# espAlarm.net
KiCad netlist of a schematic drawn in EAGLE
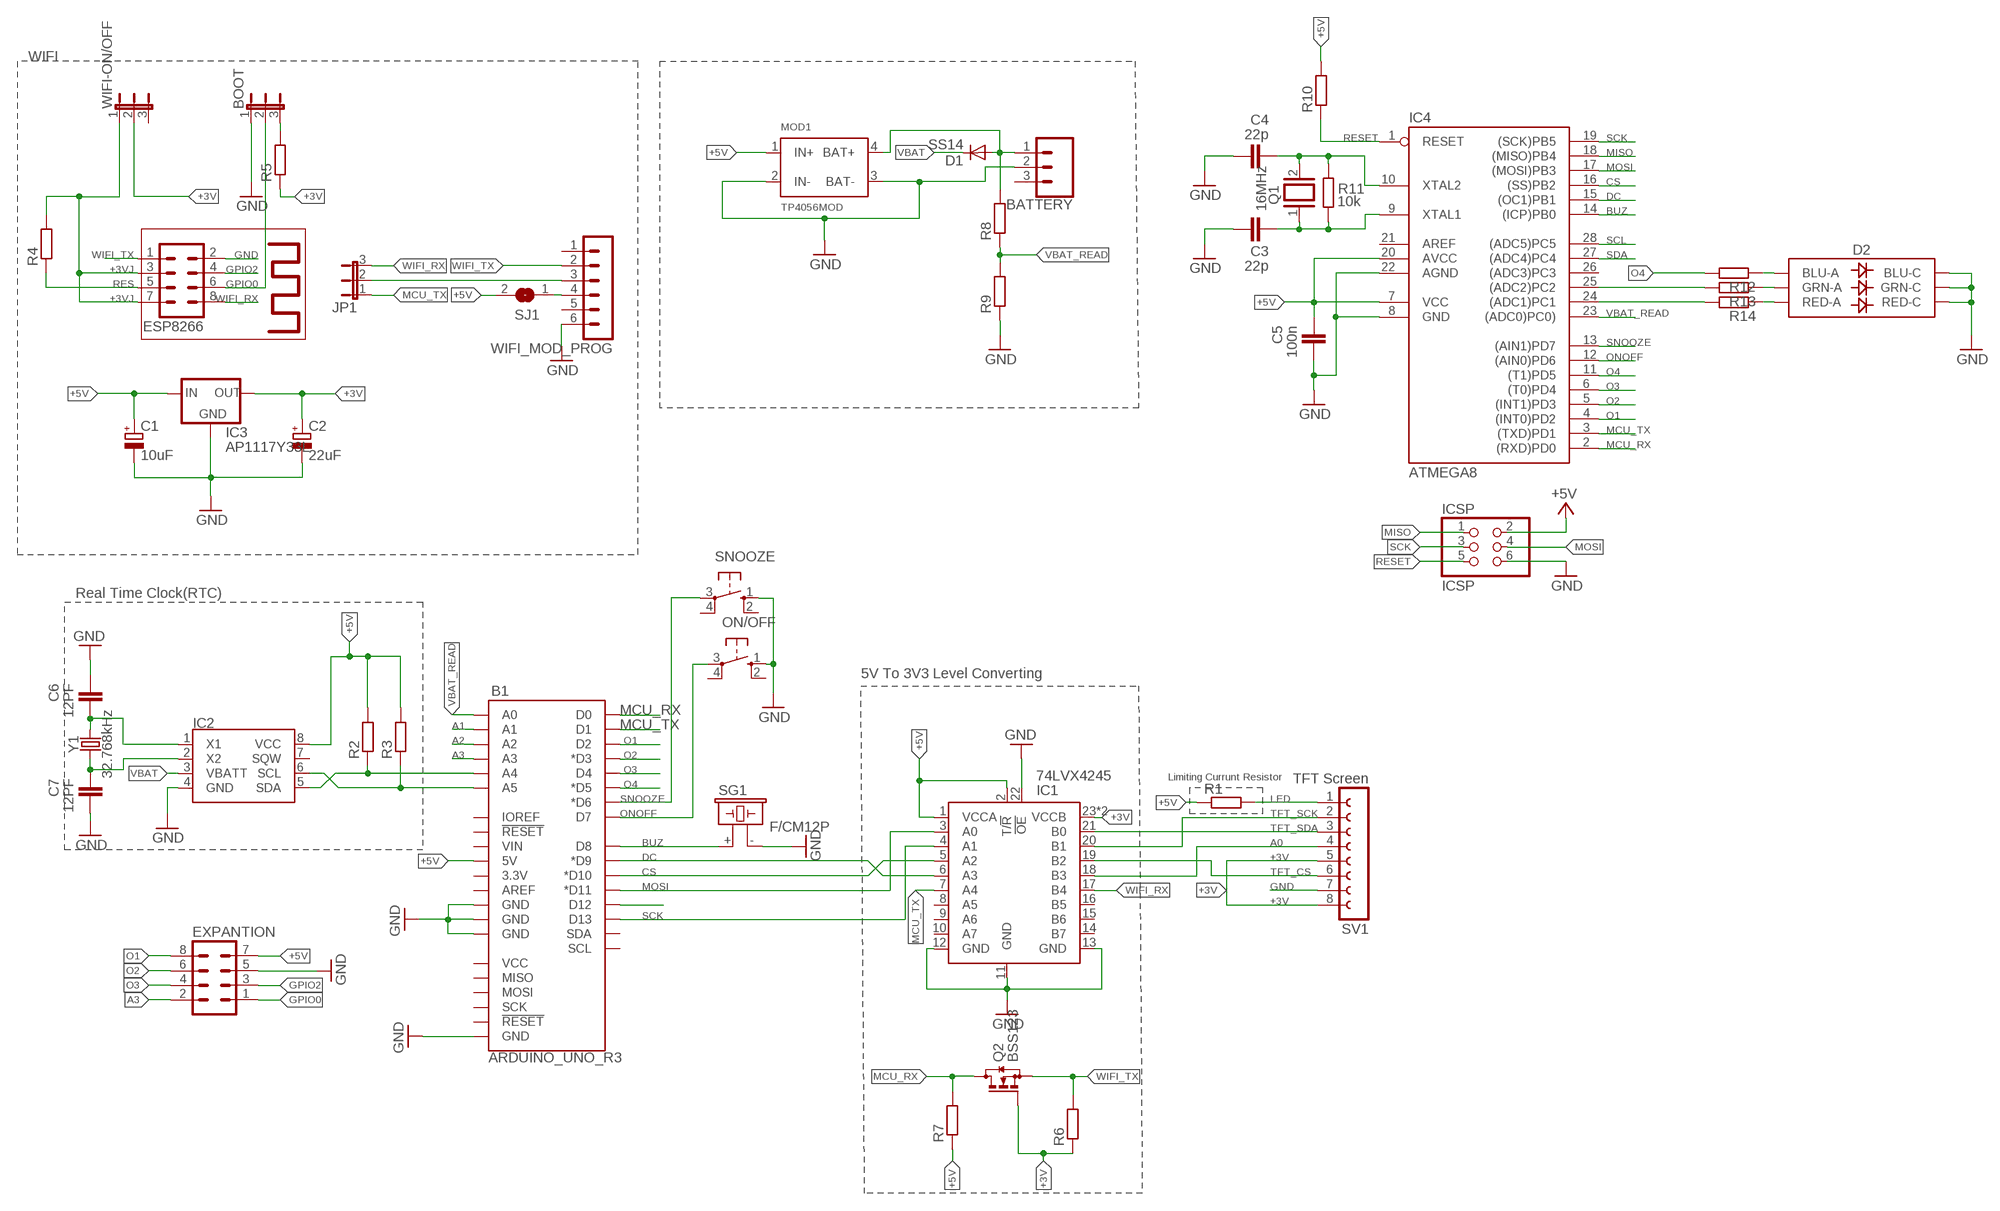
[diagram p0: schematic, sheet 1]

(export (version "E")
  (design (tool "Eeschema 10.0.6"))
  (components
    (comp (ref "B1")
      (value "ARDUINO_UNO_R3")
      (footprint "eagle-import:ARDUINO_R3")
      (libsource (lib "eagle-import") (part "ARDUINO_UNO_R3"))
    )
    (comp (ref "BATTERY")
      (value "CONN_03JST-PTH-VERT")
      (footprint "eagle-import:JST-3-PTH-VERT")
      (libsource (lib "eagle-import") (part "CONN_03JST-PTH-VERT"))
    )
    (comp (ref "BOOT")
      (value "JP2E")
      (footprint "eagle-import:JP2")
      (libsource (lib "eagle-import") (part "JP2E"))
    )
    (comp (ref "C1")
      (value "10uF")
      (footprint "eagle-import:E2,5-7")
      (libsource (lib "eagle-import") (part "CPOL-EUE2.5-7"))
    )
    (comp (ref "C2")
      (value "22uF")
      (footprint "eagle-import:E2,5-7")
      (libsource (lib "eagle-import") (part "CPOL-EUE2.5-7"))
    )
    (comp (ref "C3")
      (value "22p")
      (footprint "eagle-import:C0805")
      (libsource (lib "eagle-import") (part "C-EUC0805"))
    )
    (comp (ref "C4")
      (value "22p")
      (footprint "eagle-import:C0805")
      (libsource (lib "eagle-import") (part "C-EUC0805"))
    )
    (comp (ref "C5")
      (value "100n")
      (footprint "eagle-import:C0805")
      (libsource (lib "eagle-import") (part "C-EUC0805"))
    )
    (comp (ref "C6")
      (value "12PF")
      (footprint "eagle-import:C0805")
      (libsource (lib "eagle-import") (part "C-EUC0805"))
    )
    (comp (ref "C7")
      (value "12PF")
      (footprint "eagle-import:C0805")
      (libsource (lib "eagle-import") (part "C-EUC0805"))
    )
    (comp (ref "D1")
      (value "SS14")
      (footprint "eagle-import:DO214AC")
      (libsource (lib "eagle-import") (part "DIODE-DO214AC"))
    )
    (comp (ref "D2")
      (value "LED-RGBNO_IC")
      (footprint "eagle-import:LED-TRICOLOR-5050")
      (libsource (lib "eagle-import") (part "LED-RGBNO_IC"))
    )
    (comp (ref "ESP8266")
      (value "MA04-2")
      (footprint "eagle-import:MA04-2")
      (libsource (lib "eagle-import") (part "MA04-2"))
    )
    (comp (ref "EXPANTION")
      (value "MA04-2")
      (footprint "eagle-import:MA04-2")
      (libsource (lib "eagle-import") (part "MA04-2"))
    )
    (comp (ref "IC1")
      (value "74LVX4245")
      (footprint "eagle-import:TSSOP-24")
      (libsource (lib "eagle-import") (part "74LVX4245"))
    )
    (comp (ref "IC2")
      (value "DS1307")
      (footprint "eagle-import:DIP-08")
      (libsource (lib "eagle-import") (part "DS1307"))
    )
    (comp (ref "IC3")
      (value "AP1117Y33L")
      (footprint "eagle-import:SOT-89-3")
      (libsource (lib "eagle-import") (part "REG_FIXED"))
    )
    (comp (ref "IC4")
      (value "ATMEGA8")
      (footprint "eagle-import:DIL28-3")
      (libsource (lib "eagle-import") (part "AT90S4433P"))
    )
    (comp (ref "ICSP")
      (value "ICSP")
      (footprint "eagle-import:2X03")
      (libsource (lib "eagle-import") (part "PINHD-2X3"))
    )
    (comp (ref "JP1")
      (value "JP2E")
      (footprint "eagle-import:JP2")
      (libsource (lib "eagle-import") (part "JP2E"))
    )
    (comp (ref "MOD1")
      (value "TP4056MOD")
      (footprint "eagle-import:TP4056BRD")
      (libsource (lib "eagle-import") (part "TP4056MOD"))
    )
    (comp (ref "ON/OFF")
      (value "10-XX")
      (footprint "eagle-import:B3F-10XX")
      (fields (field (name "MPN") "B3F-1000"))
      (libsource (lib "eagle-import") (part "10-XX"))
    )
    (comp (ref "Q1")
      (value "16MHz")
      (footprint "eagle-import:SMARTPRJ_QS")
      (libsource (lib "eagle-import") (part "SMARTPRJ_XTAL/S"))
    )
    (comp (ref "Q2")
      (value "BSS123")
      (footprint "eagle-import:SOT23")
      (libsource (lib "eagle-import") (part "BSS123"))
    )
    (comp (ref "R1")
      (value "R-EU_M1206")
      (footprint "eagle-import:M1206")
      (libsource (lib "eagle-import") (part "R-EU_M1206"))
    )
    (comp (ref "R2")
      (value "R-EU_M1206")
      (footprint "eagle-import:M1206")
      (libsource (lib "eagle-import") (part "R-EU_M1206"))
    )
    (comp (ref "R3")
      (value "R-EU_M1206")
      (footprint "eagle-import:M1206")
      (libsource (lib "eagle-import") (part "R-EU_M1206"))
    )
    (comp (ref "R4")
      (value "R-EU_M1206")
      (footprint "eagle-import:M1206")
      (libsource (lib "eagle-import") (part "R-EU_M1206"))
    )
    (comp (ref "R5")
      (value "R-EU_M1206")
      (footprint "eagle-import:M1206")
      (libsource (lib "eagle-import") (part "R-EU_M1206"))
    )
    (comp (ref "R6")
      (value "R-EU_M1206")
      (footprint "eagle-import:M1206")
      (libsource (lib "eagle-import") (part "R-EU_M1206"))
    )
    (comp (ref "R7")
      (value "R-EU_M1206")
      (footprint "eagle-import:M1206")
      (libsource (lib "eagle-import") (part "R-EU_M1206"))
    )
    (comp (ref "R8")
      (value "R-EU_M1206")
      (footprint "eagle-import:M1206")
      (libsource (lib "eagle-import") (part "R-EU_M1206"))
    )
    (comp (ref "R9")
      (value "R-EU_M1206")
      (footprint "eagle-import:M1206")
      (libsource (lib "eagle-import") (part "R-EU_M1206"))
    )
    (comp (ref "R10")
      (value "R-EU_M1206")
      (footprint "eagle-import:M1206")
      (libsource (lib "eagle-import") (part "R-EU_M1206"))
    )
    (comp (ref "R11")
      (value "10k")
      (footprint "eagle-import:M1206")
      (libsource (lib "eagle-import") (part "R-EU_M1206"))
    )
    (comp (ref "R12")
      (value "R-EU_M1206")
      (footprint "eagle-import:M1206")
      (libsource (lib "eagle-import") (part "R-EU_M1206"))
    )
    (comp (ref "R13")
      (value "R-EU_M1206")
      (footprint "eagle-import:M1206")
      (libsource (lib "eagle-import") (part "R-EU_M1206"))
    )
    (comp (ref "R14")
      (value "R-EU_M1206")
      (footprint "eagle-import:M1206")
      (libsource (lib "eagle-import") (part "R-EU_M1206"))
    )
    (comp (ref "SG1")
      (value "F/CM12P")
      (footprint "eagle-import:F_CM12P")
      (libsource (lib "eagle-import") (part "F/CM12P"))
    )
    (comp (ref "SJ1") (value "SJ") (footprint "eagle-import:SJ") (libsource (lib "eagle-import") (part "SJ")))
    (comp (ref "SNOOZE")
      (value "10-XX")
      (footprint "eagle-import:B3F-10XX")
      (fields (field (name "MPN") "B3F-1000"))
      (libsource (lib "eagle-import") (part "10-XX"))
    )
    (comp (ref "SV1")
      (value "TFT Screen")
      (footprint "eagle-import:FE08")
      (libsource (lib "eagle-import") (part "FE08-1"))
    )
    (comp (ref "WIFI-ON/OFF")
      (value "JP2E")
      (footprint "eagle-import:JP2")
      (libsource (lib "eagle-import") (part "JP2E"))
    )
    (comp (ref "WIFI_MOD_PROG")
      (value "MA06-1")
      (footprint "eagle-import:MA06-1")
      (libsource (lib "eagle-import") (part "MA06-1"))
    )
    (comp (ref "Y1")
      (value "32.768kHz")
      (footprint "eagle-import:CRYSTAL-PTH-2X6-CYL")
      (libsource (lib "eagle-import") (part "CRYSTAL-32.768KHZPTH-2X6"))
    )
  )
  (nets
    (net (code "1") (name "+3V") (class "Default")
      (node (ref "C2") (pin "+") (pinfunction "+_+") (pintype "passive"))
      (node (ref "IC1") (pin "23") (pinfunction "VCCB_23") (pintype "power_in"))
      (node (ref "IC1") (pin "24") (pinfunction "VCCB_24") (pintype "power_in"))
      (node (ref "IC3") (pin "3") (pinfunction "OUT_3") (pintype "passive"))
      (node (ref "IC3") (pin "4") (pinfunction "OUT_4") (pintype "passive"))
      (node (ref "Q2") (pin "1") (pinfunction "G_1") (pintype "passive"))
      (node (ref "R5") (pin "1") (pinfunction "1_1") (pintype "passive"))
      (node (ref "R6") (pin "1") (pinfunction "1_1") (pintype "passive"))
      (node (ref "SV1") (pin "5") (pinfunction "5_5") (pintype "passive"))
      (node (ref "SV1") (pin "8") (pinfunction "8_8") (pintype "passive"))
      (node (ref "WIFI-ON/OFF") (pin "2") (pinfunction "2_2") (pintype "passive"))
    )
    (net (code "2") (name "+5V") (class "Default")
      (node (ref "B1") (pin "5V") (pinfunction "5V_5V") (pintype "bidirectional"))
      (node (ref "C1") (pin "+") (pinfunction "+_+") (pintype "passive"))
      (node (ref "C5") (pin "2") (pinfunction "2_2") (pintype "passive"))
      (node (ref "EXPANTION") (pin "7") (pinfunction "7_7") (pintype "passive"))
      (node (ref "IC1") (pin "1") (pinfunction "VCCA_1") (pintype "power_in"))
      (node (ref "IC1") (pin "2") (pinfunction "T/~{R}_2") (pintype "open_collector"))
      (node (ref "IC2") (pin "8") (pinfunction "VCC_8") (pintype "bidirectional"))
      (node (ref "IC3") (pin "1") (pinfunction "IN_1") (pintype "input"))
      (node (ref "IC4") (pin "20") (pinfunction "AVCC_20") (pintype "power_in"))
      (node (ref "IC4") (pin "7") (pinfunction "VCC_7") (pintype "power_in"))
      (node (ref "ICSP") (pin "2") (pinfunction "2_2") (pintype "passive"))
      (node (ref "MOD1") (pin "1") (pinfunction "IN+_1") (pintype "bidirectional"))
      (node (ref "R1") (pin "1") (pinfunction "1_1") (pintype "passive"))
      (node (ref "R10") (pin "2") (pinfunction "2_2") (pintype "passive"))
      (node (ref "R2") (pin "2") (pinfunction "2_2") (pintype "passive"))
      (node (ref "R3") (pin "2") (pinfunction "2_2") (pintype "passive"))
      (node (ref "R7") (pin "1") (pinfunction "1_1") (pintype "passive"))
      (node (ref "SJ1") (pin "2") (pinfunction "2_2") (pintype "passive"))
    )
    (net (code "3") (name "/+3VJ") (class "Default")
      (node (ref "ESP8266") (pin "3") (pinfunction "3_3") (pintype "passive"))
      (node (ref "ESP8266") (pin "7") (pinfunction "7_7") (pintype "passive"))
      (node (ref "R4") (pin "2") (pinfunction "2_2") (pintype "passive"))
      (node (ref "WIFI-ON/OFF") (pin "1") (pinfunction "1_1") (pintype "passive"))
    )
    (net (code "4") (name "/A0") (class "Default")
      (node (ref "IC1") (pin "18") (pinfunction "B3_18") (pintype "bidirectional"))
      (node (ref "SV1") (pin "4") (pinfunction "4_4") (pintype "passive"))
    )
    (net (code "5") (name "/A1") (class "Default")
      (node (ref "B1") (pin "A1") (pinfunction "A1_A1") (pintype "bidirectional"))
      (node (ref "IC4") (pin "24") (pinfunction "(ADC1)PC1_24") (pintype "bidirectional"))
      (node (ref "R14") (pin "2") (pinfunction "2_2") (pintype "passive"))
    )
    (net (code "6") (name "/A2") (class "Default")
      (node (ref "B1") (pin "A2") (pinfunction "A2_A2") (pintype "bidirectional"))
      (node (ref "IC4") (pin "25") (pinfunction "(ADC2)PC2_25") (pintype "bidirectional"))
      (node (ref "R13") (pin "2") (pinfunction "2_2") (pintype "passive"))
    )
    (net (code "7") (name "/AREF") (class "Default")
      (node (ref "IC4") (pin "21") (pinfunction "AREF_21") (pintype "power_in"))
    )
    (net (code "8") (name "/BUZ") (class "Default")
      (node (ref "B1") (pin "D8") (pinfunction "D8_D8") (pintype "bidirectional"))
      (node (ref "IC4") (pin "14") (pinfunction "(ICP)PB0_14") (pintype "bidirectional"))
      (node (ref "SG1") (pin "+") (pinfunction "1_+") (pintype "passive"))
    )
    (net (code "9") (name "/CS") (class "Default")
      (node (ref "B1") (pin "D10") (pinfunction "*D10_D10") (pintype "bidirectional"))
      (node (ref "IC1") (pin "5") (pinfunction "A2_5") (pintype "bidirectional"))
      (node (ref "IC4") (pin "16") (pinfunction "(SS)PB2_16") (pintype "bidirectional"))
    )
    (net (code "10") (name "/DC") (class "Default")
      (node (ref "B1") (pin "D9") (pinfunction "*D9_D9") (pintype "bidirectional"))
      (node (ref "IC1") (pin "6") (pinfunction "A3_6") (pintype "bidirectional"))
      (node (ref "IC4") (pin "15") (pinfunction "(OC1)PB1_15") (pintype "bidirectional"))
    )
    (net (code "11") (name "/LED") (class "Default")
      (node (ref "R1") (pin "2") (pinfunction "2_2") (pintype "passive"))
      (node (ref "SV1") (pin "1") (pinfunction "1_1") (pintype "passive"))
    )
    (net (code "12") (name "/ONOFF") (class "Default")
      (node (ref "B1") (pin "D7") (pinfunction "D7_D7") (pintype "bidirectional"))
      (node (ref "IC4") (pin "12") (pinfunction "(AIN0)PD6_12") (pintype "bidirectional"))
      (node (ref "ON/OFF") (pin "3") (pinfunction "P_3") (pintype "passive"))
    )
    (net (code "13") (name "/RES") (class "Default")
      (node (ref "ESP8266") (pin "5") (pinfunction "5_5") (pintype "passive"))
      (node (ref "R4") (pin "1") (pinfunction "1_1") (pintype "passive"))
    )
    (net (code "14") (name "/SCL") (class "Default")
      (node (ref "B1") (pin "A5") (pinfunction "A5_A5") (pintype "bidirectional"))
      (node (ref "IC2") (pin "6") (pinfunction "SCL_6") (pintype "bidirectional"))
      (node (ref "IC4") (pin "28") (pinfunction "(ADC5)PC5_28") (pintype "bidirectional"))
      (node (ref "R3") (pin "1") (pinfunction "1_1") (pintype "passive"))
    )
    (net (code "15") (name "/SDA") (class "Default")
      (node (ref "B1") (pin "A4") (pinfunction "A4_A4") (pintype "bidirectional"))
      (node (ref "IC2") (pin "5") (pinfunction "SDA_5") (pintype "bidirectional"))
      (node (ref "IC4") (pin "27") (pinfunction "(ADC4)PC4_27") (pintype "bidirectional"))
      (node (ref "R2") (pin "1") (pinfunction "1_1") (pintype "passive"))
    )
    (net (code "16") (name "/SNOOZE") (class "Default")
      (node (ref "B1") (pin "D6") (pinfunction "*D6_D6") (pintype "bidirectional"))
      (node (ref "IC4") (pin "13") (pinfunction "(AIN1)PD7_13") (pintype "bidirectional"))
      (node (ref "SNOOZE") (pin "3") (pinfunction "P_3") (pintype "passive"))
    )
    (net (code "17") (name "/TFT_CS") (class "Default")
      (node (ref "IC1") (pin "19") (pinfunction "B2_19") (pintype "bidirectional"))
      (node (ref "SV1") (pin "6") (pinfunction "6_6") (pintype "passive"))
    )
    (net (code "18") (name "/TFT_SCK") (class "Default")
      (node (ref "IC1") (pin "20") (pinfunction "B1_20") (pintype "bidirectional"))
      (node (ref "SV1") (pin "2") (pinfunction "2_2") (pintype "passive"))
    )
    (net (code "19") (name "/TFT_SDA") (class "Default")
      (node (ref "IC1") (pin "21") (pinfunction "B0_21") (pintype "bidirectional"))
      (node (ref "SV1") (pin "3") (pinfunction "3_3") (pintype "passive"))
    )
    (net (code "20") (name "A3") (class "Default")
      (node (ref "B1") (pin "A3") (pinfunction "A3_A3") (pintype "bidirectional"))
      (node (ref "EXPANTION") (pin "2") (pinfunction "2_2") (pintype "passive"))
    )
    (net (code "21") (name "GND") (class "Default")
      (node (ref "B1") (pin "GND@1") (pinfunction "GND_GND@1") (pintype "bidirectional"))
      (node (ref "B1") (pin "GND@2") (pinfunction "GND_GND@2") (pintype "bidirectional"))
      (node (ref "B1") (pin "GND@3") (pinfunction "GND_GND@3") (pintype "bidirectional"))
      (node (ref "B1") (pin "GND@4") (pinfunction "GND_GND@4") (pintype "bidirectional"))
      (node (ref "BATTERY") (pin "2") (pinfunction "2_2") (pintype "passive"))
      (node (ref "BOOT") (pin "1") (pinfunction "1_1") (pintype "passive"))
      (node (ref "C1") (pin "-") (pinfunction "-_-") (pintype "passive"))
      (node (ref "C2") (pin "-") (pinfunction "-_-") (pintype "passive"))
      (node (ref "C3") (pin "1") (pinfunction "1_1") (pintype "passive"))
      (node (ref "C4") (pin "1") (pinfunction "1_1") (pintype "passive"))
      (node (ref "C5") (pin "1") (pinfunction "1_1") (pintype "passive"))
      (node (ref "C6") (pin "2") (pinfunction "2_2") (pintype "passive"))
      (node (ref "C7") (pin "1") (pinfunction "1_1") (pintype "passive"))
      (node (ref "D2") (pin "4") (pinfunction "BLU-C_4") (pintype "bidirectional"))
      (node (ref "D2") (pin "5") (pinfunction "RED-C_5") (pintype "bidirectional"))
      (node (ref "D2") (pin "6") (pinfunction "GRN-C_6") (pintype "bidirectional"))
      (node (ref "ESP8266") (pin "2") (pinfunction "2_2") (pintype "passive"))
      (node (ref "EXPANTION") (pin "5") (pinfunction "5_5") (pintype "passive"))
      (node (ref "IC1") (pin "11") (pinfunction "GND_11") (pintype "power_in"))
      (node (ref "IC1") (pin "12") (pinfunction "GND_12") (pintype "power_in"))
      (node (ref "IC1") (pin "13") (pinfunction "GND_13") (pintype "power_in"))
      (node (ref "IC1") (pin "22") (pinfunction "~{OE}_22") (pintype "open_collector"))
      (node (ref "IC2") (pin "4") (pinfunction "GND_4") (pintype "bidirectional"))
      (node (ref "IC3") (pin "2") (pinfunction "GND_2") (pintype "input"))
      (node (ref "IC4") (pin "22") (pinfunction "AGND_22") (pintype "power_in"))
      (node (ref "IC4") (pin "8") (pinfunction "GND_8") (pintype "power_in"))
      (node (ref "ICSP") (pin "6") (pinfunction "6_6") (pintype "passive"))
      (node (ref "MOD1") (pin "2") (pinfunction "IN-_2") (pintype "bidirectional"))
      (node (ref "MOD1") (pin "3") (pinfunction "BAT-_3") (pintype "bidirectional"))
      (node (ref "ON/OFF") (pin "1") (pinfunction "S_1") (pintype "passive"))
      (node (ref "R9") (pin "1") (pinfunction "1_1") (pintype "passive"))
      (node (ref "SG1") (pin "-") (pinfunction "2_-") (pintype "passive"))
      (node (ref "SNOOZE") (pin "1") (pinfunction "S_1") (pintype "passive"))
      (node (ref "SV1") (pin "7") (pinfunction "7_7") (pintype "passive"))
      (node (ref "WIFI_MOD_PROG") (pin "6") (pinfunction "6_6") (pintype "passive"))
    )
    (net (code "22") (name "GPIO0") (class "Default")
      (node (ref "BOOT") (pin "2") (pinfunction "2_2") (pintype "passive"))
      (node (ref "ESP8266") (pin "6") (pinfunction "6_6") (pintype "passive"))
      (node (ref "EXPANTION") (pin "1") (pinfunction "1_1") (pintype "passive"))
    )
    (net (code "23") (name "GPIO2") (class "Default")
      (node (ref "ESP8266") (pin "4") (pinfunction "4_4") (pintype "passive"))
      (node (ref "EXPANTION") (pin "3") (pinfunction "3_3") (pintype "passive"))
    )
    (net (code "24") (name "MCU_RX") (class "Default")
      (node (ref "B1") (pin "D0") (pinfunction "D0_D0") (pintype "bidirectional"))
      (node (ref "IC4") (pin "2") (pinfunction "(RXD)PD0_2") (pintype "bidirectional"))
      (node (ref "Q2") (pin "3") (pinfunction "D_3") (pintype "passive"))
      (node (ref "R7") (pin "2") (pinfunction "2_2") (pintype "passive"))
    )
    (net (code "25") (name "MCU_TX") (class "Default")
      (node (ref "B1") (pin "D1") (pinfunction "D1_D1") (pintype "bidirectional"))
      (node (ref "IC1") (pin "7") (pinfunction "A4_7") (pintype "bidirectional"))
      (node (ref "IC4") (pin "3") (pinfunction "(TXD)PD1_3") (pintype "bidirectional"))
      (node (ref "JP1") (pin "1") (pinfunction "1_1") (pintype "passive"))
    )
    (net (code "26") (name "MISO") (class "Default")
      (node (ref "IC4") (pin "18") (pinfunction "(MISO)PB4_18") (pintype "bidirectional"))
      (node (ref "ICSP") (pin "1") (pinfunction "1_1") (pintype "passive"))
    )
    (net (code "27") (name "MOSI") (class "Default")
      (node (ref "B1") (pin "D11") (pinfunction "*D11_D11") (pintype "bidirectional"))
      (node (ref "IC1") (pin "3") (pinfunction "A0_3") (pintype "bidirectional"))
      (node (ref "IC4") (pin "17") (pinfunction "(MOSI)PB3_17") (pintype "bidirectional"))
      (node (ref "ICSP") (pin "4") (pinfunction "4_4") (pintype "passive"))
    )
    (net (code "28") (name "Net-(BOOT-Pad3)") (class "Default")
      (node (ref "BOOT") (pin "3") (pinfunction "3_3") (pintype "passive"))
      (node (ref "R5") (pin "2") (pinfunction "2_2") (pintype "passive"))
    )
    (net (code "29") (name "Net-(D2-BLU-A)") (class "Default")
      (node (ref "D2") (pin "3") (pinfunction "BLU-A_3") (pintype "bidirectional"))
      (node (ref "R12") (pin "1") (pinfunction "1_1") (pintype "passive"))
    )
    (net (code "30") (name "Net-(D2-GRN-A)") (class "Default")
      (node (ref "D2") (pin "1") (pinfunction "GRN-A_1") (pintype "bidirectional"))
      (node (ref "R13") (pin "1") (pinfunction "1_1") (pintype "passive"))
    )
    (net (code "31") (name "Net-(D2-RED-A)") (class "Default")
      (node (ref "D2") (pin "2") (pinfunction "RED-A_2") (pintype "bidirectional"))
      (node (ref "R14") (pin "1") (pinfunction "1_1") (pintype "passive"))
    )
    (net (code "32") (name "Net-(IC2-X1)") (class "Default")
      (node (ref "C6") (pin "1") (pinfunction "1_1") (pintype "passive"))
      (node (ref "IC2") (pin "1") (pinfunction "X1_1") (pintype "bidirectional"))
      (node (ref "Y1") (pin "2") (pinfunction "2_2") (pintype "passive"))
    )
    (net (code "33") (name "Net-(IC2-X2)") (class "Default")
      (node (ref "C7") (pin "2") (pinfunction "2_2") (pintype "passive"))
      (node (ref "IC2") (pin "2") (pinfunction "X2_2") (pintype "bidirectional"))
      (node (ref "Y1") (pin "1") (pinfunction "1_1") (pintype "passive"))
    )
    (net (code "34") (name "Net-(IC4-XTAL1)") (class "Default")
      (node (ref "C3") (pin "2") (pinfunction "2_2") (pintype "passive"))
      (node (ref "IC4") (pin "9") (pinfunction "XTAL1_9") (pintype "bidirectional"))
      (node (ref "Q1") (pin "1") (pinfunction "1_1") (pintype "passive"))
      (node (ref "R11") (pin "1") (pinfunction "1_1") (pintype "passive"))
    )
    (net (code "35") (name "Net-(IC4-XTAL2)") (class "Default")
      (node (ref "C4") (pin "2") (pinfunction "2_2") (pintype "passive"))
      (node (ref "IC4") (pin "10") (pinfunction "XTAL2_10") (pintype "bidirectional"))
      (node (ref "Q1") (pin "2") (pinfunction "2_2") (pintype "passive"))
      (node (ref "R11") (pin "2") (pinfunction "2_2") (pintype "passive"))
    )
    (net (code "36") (name "Net-(JP1-Pad2)") (class "Default")
      (node (ref "JP1") (pin "2") (pinfunction "2_2") (pintype "passive"))
      (node (ref "WIFI_MOD_PROG") (pin "3") (pinfunction "3_3") (pintype "passive"))
    )
    (net (code "37") (name "Net-(MOD1-BAT+)") (class "Default")
      (node (ref "BATTERY") (pin "1") (pinfunction "1_1") (pintype "passive"))
      (node (ref "D1") (pin "A") (pinfunction "A_A") (pintype "passive"))
      (node (ref "MOD1") (pin "4") (pinfunction "BAT+_4") (pintype "bidirectional"))
      (node (ref "R8") (pin "2") (pinfunction "2_2") (pintype "passive"))
    )
    (net (code "38") (name "Net-(SJ1-Pad1)") (class "Default")
      (node (ref "SJ1") (pin "1") (pinfunction "1_1") (pintype "passive"))
      (node (ref "WIFI_MOD_PROG") (pin "4") (pinfunction "4_4") (pintype "passive"))
    )
    (net (code "39") (name "O1") (class "Default")
      (node (ref "B1") (pin "D2") (pinfunction "D2_D2") (pintype "bidirectional"))
      (node (ref "EXPANTION") (pin "8") (pinfunction "8_8") (pintype "passive"))
      (node (ref "IC4") (pin "4") (pinfunction "(INT0)PD2_4") (pintype "bidirectional"))
    )
    (net (code "40") (name "O2") (class "Default")
      (node (ref "B1") (pin "D3") (pinfunction "*D3_D3") (pintype "bidirectional"))
      (node (ref "EXPANTION") (pin "6") (pinfunction "6_6") (pintype "passive"))
      (node (ref "IC4") (pin "5") (pinfunction "(INT1)PD3_5") (pintype "bidirectional"))
    )
    (net (code "41") (name "O3") (class "Default")
      (node (ref "B1") (pin "D4") (pinfunction "D4_D4") (pintype "bidirectional"))
      (node (ref "EXPANTION") (pin "4") (pinfunction "4_4") (pintype "passive"))
      (node (ref "IC4") (pin "6") (pinfunction "(T0)PD4_6") (pintype "bidirectional"))
    )
    (net (code "42") (name "O4") (class "Default")
      (node (ref "B1") (pin "D5") (pinfunction "*D5_D5") (pintype "bidirectional"))
      (node (ref "IC4") (pin "11") (pinfunction "(T1)PD5_11") (pintype "bidirectional"))
      (node (ref "R12") (pin "2") (pinfunction "2_2") (pintype "passive"))
    )
    (net (code "43") (name "RESET") (class "Default")
      (node (ref "IC4") (pin "1") (pinfunction "RESET_1") (pintype "input"))
      (node (ref "ICSP") (pin "5") (pinfunction "5_5") (pintype "passive"))
      (node (ref "R10") (pin "1") (pinfunction "1_1") (pintype "passive"))
    )
    (net (code "44") (name "SCK") (class "Default")
      (node (ref "B1") (pin "D13") (pinfunction "D13_D13") (pintype "bidirectional"))
      (node (ref "IC1") (pin "4") (pinfunction "A1_4") (pintype "bidirectional"))
      (node (ref "IC4") (pin "19") (pinfunction "(SCK)PB5_19") (pintype "bidirectional"))
      (node (ref "ICSP") (pin "3") (pinfunction "3_3") (pintype "passive"))
    )
    (net (code "45") (name "VBAT") (class "Default")
      (node (ref "D1") (pin "C") (pinfunction "C_C") (pintype "passive"))
      (node (ref "IC2") (pin "3") (pinfunction "VBATT_3") (pintype "bidirectional"))
    )
    (net (code "46") (name "VBAT_READ") (class "Default")
      (node (ref "B1") (pin "A0") (pinfunction "A0_A0") (pintype "bidirectional"))
      (node (ref "IC4") (pin "23") (pinfunction "(ADC0)PC0)_23") (pintype "bidirectional"))
      (node (ref "R8") (pin "1") (pinfunction "1_1") (pintype "passive"))
      (node (ref "R9") (pin "2") (pinfunction "2_2") (pintype "passive"))
    )
    (net (code "47") (name "WIFI_RX") (class "Default")
      (node (ref "ESP8266") (pin "8") (pinfunction "8_8") (pintype "passive"))
      (node (ref "IC1") (pin "17") (pinfunction "B4_17") (pintype "bidirectional"))
      (node (ref "JP1") (pin "3") (pinfunction "3_3") (pintype "passive"))
    )
    (net (code "48") (name "WIFI_TX") (class "Default")
      (node (ref "ESP8266") (pin "1") (pinfunction "1_1") (pintype "passive"))
      (node (ref "Q2") (pin "2") (pinfunction "S_2") (pintype "passive"))
      (node (ref "R6") (pin "2") (pinfunction "2_2") (pintype "passive"))
      (node (ref "WIFI_MOD_PROG") (pin "2") (pinfunction "2_2") (pintype "passive"))
    )
    (net (code "49") (name "unconnected-(B1-Pad3.3V)") (class "Default")
      (node (ref "B1") (pin "3.3V") (pinfunction "3.3V_3.3V") (pintype "bidirectional"))
    )
    (net (code "50") (name "unconnected-(B1-PadAREF)") (class "Default")
      (node (ref "B1") (pin "AREF") (pinfunction "AREF_AREF") (pintype "bidirectional"))
    )
    (net (code "51") (name "unconnected-(B1-PadD12)") (class "Default")
      (node (ref "B1") (pin "D12") (pinfunction "D12_D12") (pintype "bidirectional"))
    )
    (net (code "52") (name "unconnected-(B1-PadIOREF)") (class "Default")
      (node (ref "B1") (pin "IOREF") (pinfunction "IOREF_IOREF") (pintype "bidirectional"))
    )
    (net (code "53") (name "unconnected-(B1-PadMISO)") (class "Default")
      (node (ref "B1") (pin "MISO") (pinfunction "MISO_MISO") (pintype "bidirectional"))
    )
    (net (code "54") (name "unconnected-(B1-PadMOSI)") (class "Default")
      (node (ref "B1") (pin "MOSI") (pinfunction "MOSI_MOSI") (pintype "bidirectional"))
    )
    (net (code "55") (name "unconnected-(B1-PadSCK)") (class "Default")
      (node (ref "B1") (pin "SCK") (pinfunction "SCK_SCK") (pintype "bidirectional"))
    )
    (net (code "56") (name "unconnected-(B1-PadSCL)") (class "Default")
      (node (ref "B1") (pin "SCL") (pinfunction "SCL_SCL") (pintype "bidirectional"))
    )
    (net (code "57") (name "unconnected-(B1-PadSDA)") (class "Default")
      (node (ref "B1") (pin "SDA") (pinfunction "SDA_SDA") (pintype "bidirectional"))
    )
    (net (code "58") (name "unconnected-(B1-PadVCC)") (class "Default")
      (node (ref "B1") (pin "VCC") (pinfunction "VCC_VCC") (pintype "bidirectional"))
    )
    (net (code "59") (name "unconnected-(B1-PadVIN)") (class "Default")
      (node (ref "B1") (pin "VIN") (pinfunction "VIN_VIN") (pintype "bidirectional"))
    )
    (net (code "60") (name "unconnected-(B1-~{RESET}-PadRESET@1)") (class "Default")
      (node (ref "B1") (pin "RESET@1") (pinfunction "~{RESET}_RESET@1") (pintype "bidirectional"))
    )
    (net (code "61") (name "unconnected-(B1-~{RESET}-PadRESET@2)") (class "Default")
      (node (ref "B1") (pin "RESET@2") (pinfunction "~{RESET}_RESET@2") (pintype "bidirectional"))
    )
    (net (code "62") (name "unconnected-(BATTERY-Pad3)") (class "Default")
      (node (ref "BATTERY") (pin "3") (pinfunction "3_3") (pintype "passive"))
    )
    (net (code "63") (name "unconnected-(IC1-A5-Pad8)") (class "Default")
      (node (ref "IC1") (pin "8") (pinfunction "A5_8") (pintype "bidirectional"))
    )
    (net (code "64") (name "unconnected-(IC1-A6-Pad9)") (class "Default")
      (node (ref "IC1") (pin "9") (pinfunction "A6_9") (pintype "bidirectional"))
    )
    (net (code "65") (name "unconnected-(IC1-A7-Pad10)") (class "Default")
      (node (ref "IC1") (pin "10") (pinfunction "A7_10") (pintype "bidirectional"))
    )
    (net (code "66") (name "unconnected-(IC1-B5-Pad16)") (class "Default")
      (node (ref "IC1") (pin "16") (pinfunction "B5_16") (pintype "bidirectional"))
    )
    (net (code "67") (name "unconnected-(IC1-B6-Pad15)") (class "Default")
      (node (ref "IC1") (pin "15") (pinfunction "B6_15") (pintype "bidirectional"))
    )
    (net (code "68") (name "unconnected-(IC1-B7-Pad14)") (class "Default")
      (node (ref "IC1") (pin "14") (pinfunction "B7_14") (pintype "bidirectional"))
    )
    (net (code "69") (name "unconnected-(IC2-SQW-Pad7)") (class "Default")
      (node (ref "IC2") (pin "7") (pinfunction "SQW_7") (pintype "bidirectional"))
    )
    (net (code "70") (name "unconnected-(IC4-(ADC3)PC3-Pad26)") (class "Default")
      (node (ref "IC4") (pin "26") (pinfunction "(ADC3)PC3_26") (pintype "bidirectional"))
    )
    (net (code "71") (name "unconnected-(ON/OFF-P1-Pad4)") (class "Default")
      (node (ref "ON/OFF") (pin "4") (pinfunction "P1_4") (pintype "passive"))
    )
    (net (code "72") (name "unconnected-(ON/OFF-S1-Pad2)") (class "Default")
      (node (ref "ON/OFF") (pin "2") (pinfunction "S1_2") (pintype "passive"))
    )
    (net (code "73") (name "unconnected-(SNOOZE-P1-Pad4)") (class "Default")
      (node (ref "SNOOZE") (pin "4") (pinfunction "P1_4") (pintype "passive"))
    )
    (net (code "74") (name "unconnected-(SNOOZE-S1-Pad2)") (class "Default")
      (node (ref "SNOOZE") (pin "2") (pinfunction "S1_2") (pintype "passive"))
    )
    (net (code "75") (name "unconnected-(WIFI-ON/OFF-Pad3)") (class "Default")
      (node (ref "WIFI-ON/OFF") (pin "3") (pinfunction "3_3") (pintype "passive"))
    )
    (net (code "76") (name "unconnected-(WIFI_MOD_PROG-Pad1)") (class "Default")
      (node (ref "WIFI_MOD_PROG") (pin "1") (pinfunction "1_1") (pintype "passive"))
    )
    (net (code "77") (name "unconnected-(WIFI_MOD_PROG-Pad5)") (class "Default")
      (node (ref "WIFI_MOD_PROG") (pin "5") (pinfunction "5_5") (pintype "passive"))
    )
  )
)
